# plc_module_xs_00001_001_Power.net
KiCad netlist of a schematic drawn in Altium Designer
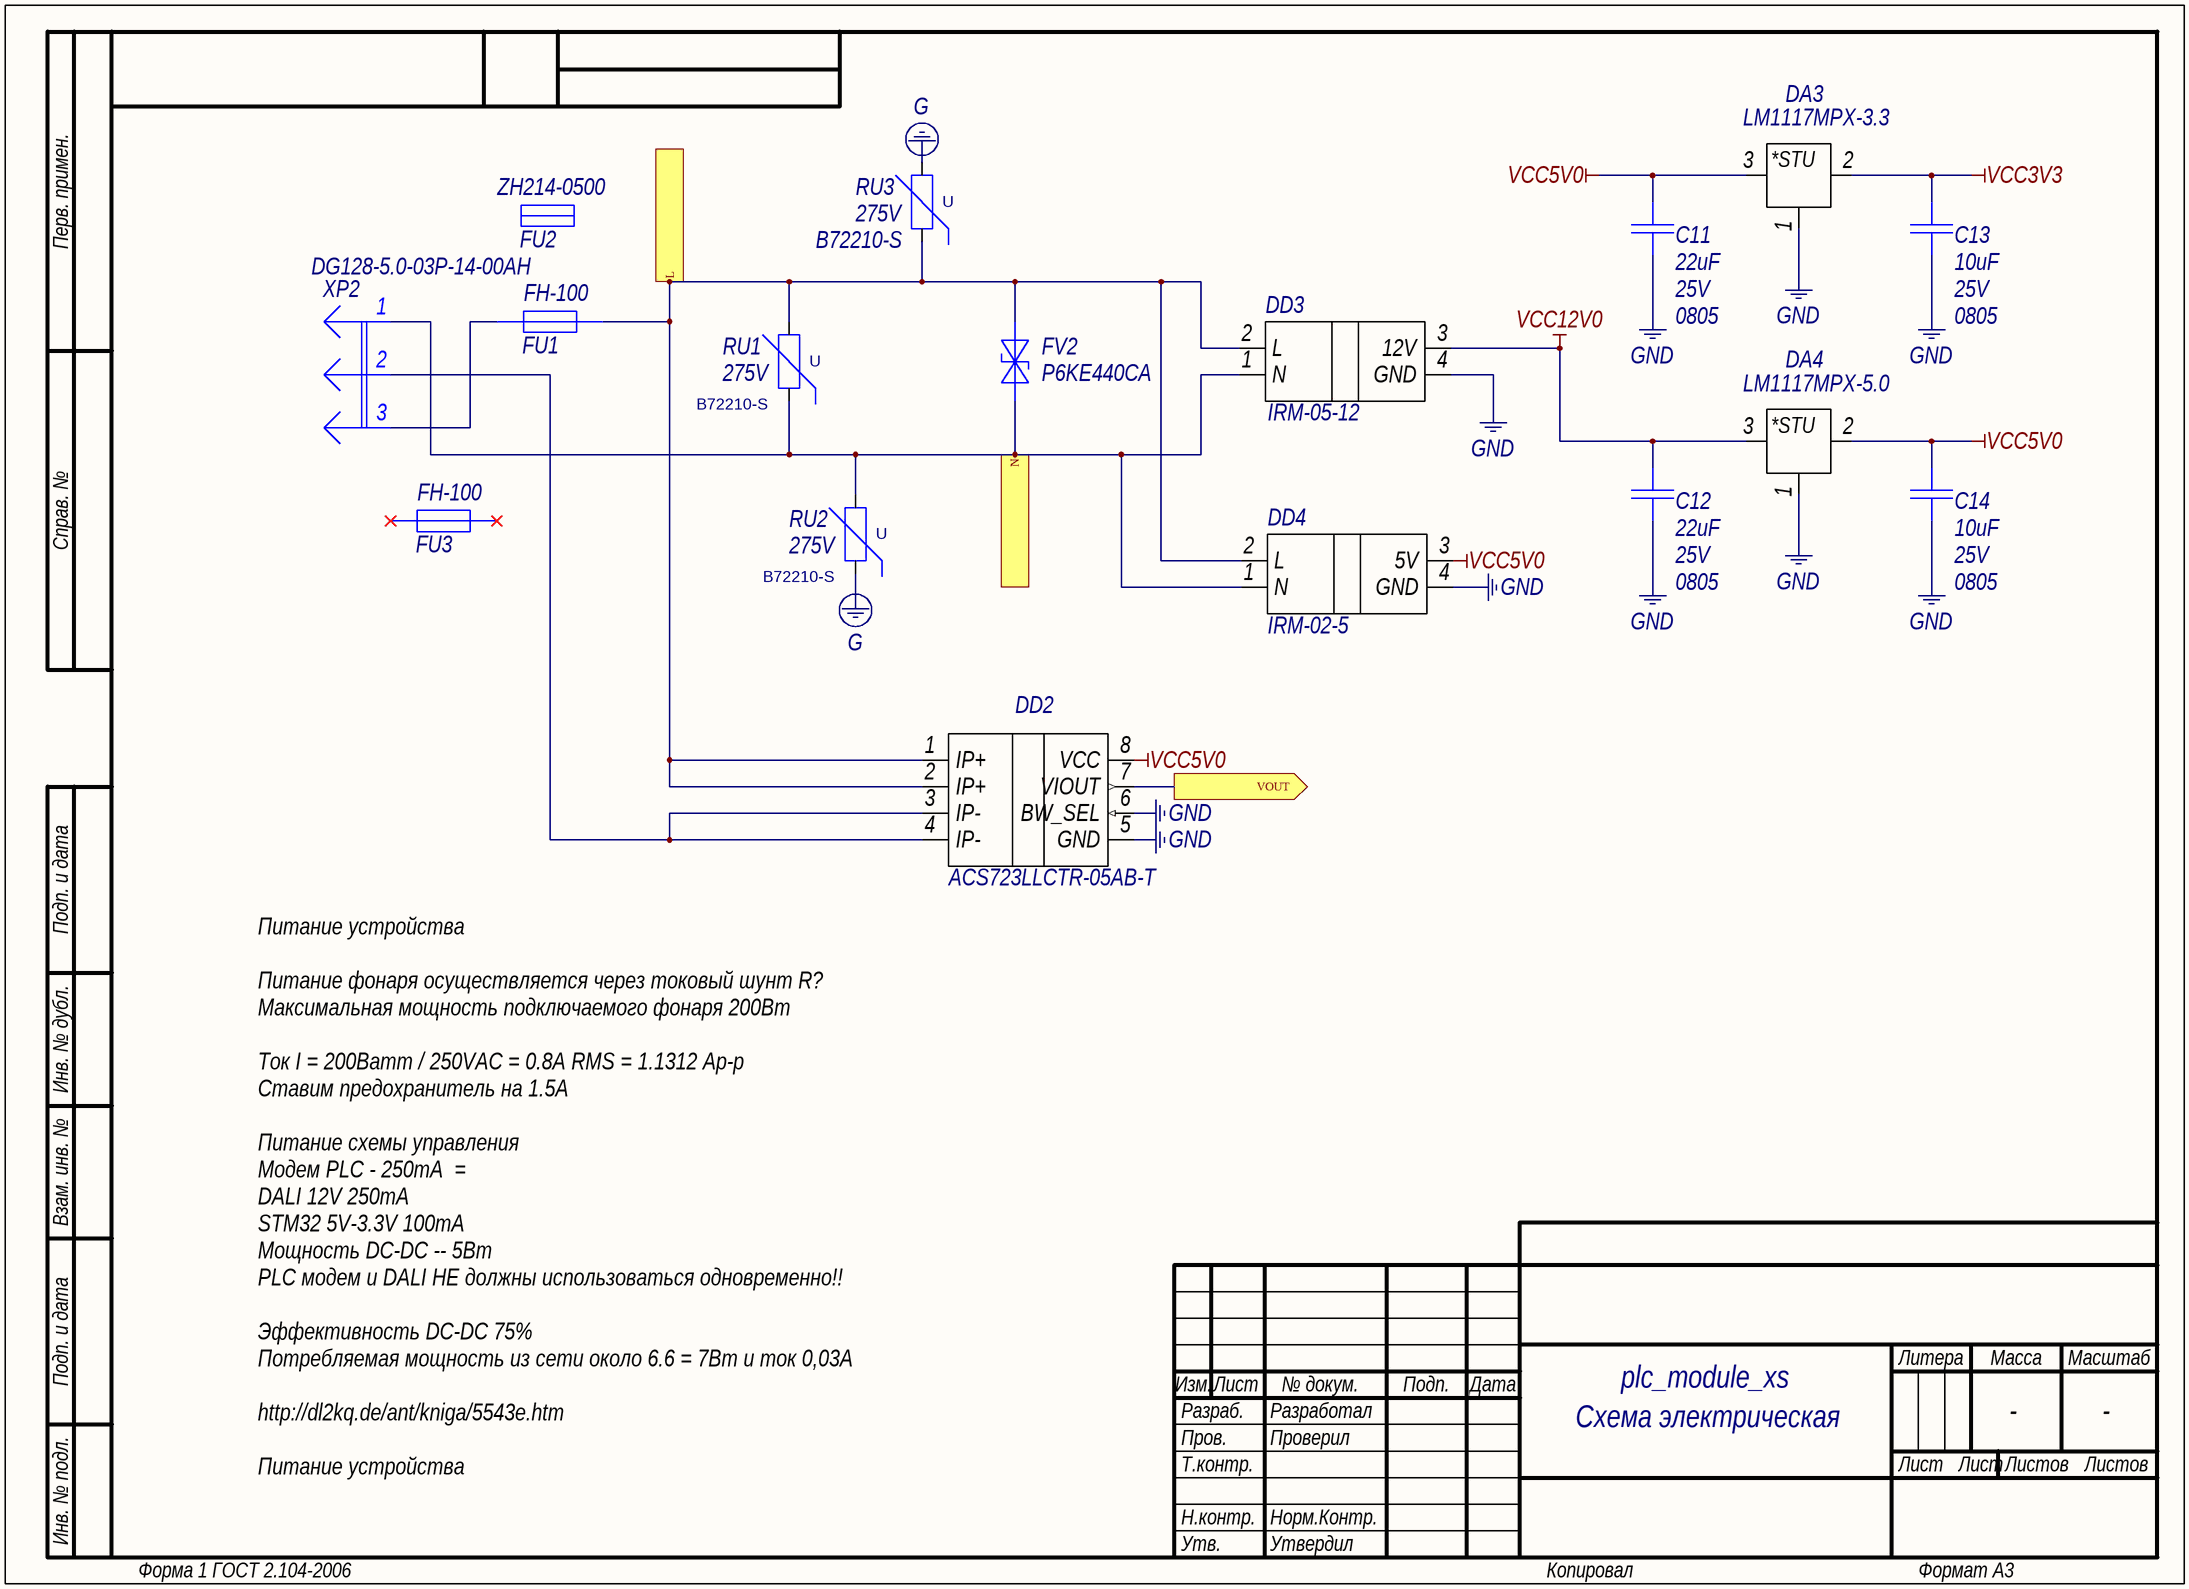
[diagram p0: plc_module_xs.00001.001_Power.SchDoc]

(export (version "E")
  (design (tool "Eeschema 10.0.6"))
  (components
    (comp (ref "C11")
      (value "22uF")
      (footprint "0805")
      (fields
        (field (name "PART NUMBER") "GRM21BR61E226ME44L")
        (field (name "VOLTAGE") "25V")
        (field (name "TOLERANCE") "±20%")
        (field (name "MANUFACTURER") "Murata")
        (field (name "PUBLISHER") "Andrew Danich")
      )
      (libsource (lib "GOST_IMPORT_PARTS") (part "Capacitor"))
    )
    (comp (ref "C12")
      (value "22uF")
      (footprint "0805")
      (fields
        (field (name "PART NUMBER") "GRM21BR61E226ME44L")
        (field (name "VOLTAGE") "25V")
        (field (name "TOLERANCE") "±20%")
        (field (name "MANUFACTURER") "Murata")
        (field (name "PUBLISHER") "Andrew Danich")
      )
      (libsource (lib "GOST_IMPORT_PARTS") (part "Capacitor"))
    )
    (comp (ref "C13")
      (value "10uF")
      (footprint "0805")
      (fields
        (field (name "PART NUMBER") "GRM21BR61E106KA73L")
        (field (name "VOLTAGE") "25V")
        (field (name "TOLERANCE") "±10%")
        (field (name "MANUFACTURER") "Murata")
        (field (name "PUBLISHER") "Andrew Danich")
      )
      (libsource (lib "GOST_IMPORT_PARTS") (part "Capacitor"))
    )
    (comp (ref "C14")
      (value "10uF")
      (footprint "0805")
      (fields
        (field (name "PART NUMBER") "GRM21BR61E106KA73L")
        (field (name "VOLTAGE") "25V")
        (field (name "TOLERANCE") "±10%")
        (field (name "MANUFACTURER") "Murata")
        (field (name "PUBLISHER") "Andrew Danich")
      )
      (libsource (lib "GOST_IMPORT_PARTS") (part "Capacitor"))
    )
    (comp (ref "DA3")
      (value "LM1117MPX-3.3")
      (footprint "SOT-223")
      (fields (field (name "Comment") "LM1117-Series") (field (name "PUBLISHER") "Andrew Danich"))
      (libsource (lib "GOST_IMPORT_PARTS") (part "LM1117-Series"))
    )
    (comp (ref "DA4")
      (value "LM1117MPX-5.0")
      (footprint "SOT-223")
      (fields (field (name "Comment") "LM1117-Series") (field (name "PUBLISHER") "Andrew Danich"))
      (libsource (lib "GOST_IMPORT_PARTS") (part "LM1117-Series"))
    )
    (comp (ref "DD2")
      (value "ACS723LLCTR-05AB-T")
      (footprint "SOIC-8")
      (fields (field (name "PART NUMBER") "ACS723LLCTR-05AB-T") (field (name "PUBLISHER") "Andrew Danich"))
      (libsource (lib "GOST_IMPORT_PARTS") (part "ACS723LLC"))
    )
    (comp (ref "DD3")
      (value "IRM-05-12")
      (footprint "IRM-05-12")
      (fields (field (name "POWER") "5W") (field (name "MANUFACTURER") "Mean Well (MW)"))
      (libsource (lib "GOST_IMPORT_PARTS") (part "IRM-05-12"))
    )
    (comp (ref "DD4")
      (value "IRM-02-5")
      (footprint "IRM-02-5")
      (fields (field (name "POWER") "2W") (field (name "MANUFACTURER") "Mean Well (MW)"))
      (libsource (lib "GOST_IMPORT_PARTS") (part "IRM-02-5"))
    )
    (comp (ref "FU1")
      (value "FH-100")
      (footprint "F-W20.0/E5.0")
      (fields (field (name "Comment") "Fuse") (field (name "PUBLISHER") "Andrew Danich"))
      (libsource (lib "GOST_IMPORT_PARTS") (part "Fuse"))
    )
    (comp (ref "FU2")
      (value "ZH214-0500")
      (footprint "FUSE_SCHURTER_FSF5X20")
      (fields (field (name "MANUFACTURER") "Zhenhui") (field (name "PUBLISHER") "Andrew Danich"))
      (libsource (lib "GOST_IMPORT_PARTS") (part "Fuse_1"))
    )
    (comp (ref "FU3")
      (value "FH-100")
      (footprint "F-W20.0/E5.0")
      (fields (field (name "Comment") "Fuse") (field (name "PUBLISHER") "Andrew Danich"))
      (libsource (lib "GOST_IMPORT_PARTS") (part "Fuse"))
    )
    (comp (ref "FV2")
      (value "P6KE440CA")
      (footprint "DO-15")
      (fields (field (name "PART NUMBER") "P6KE440CA") (field (name "PUBLISHER") "Andrew Danich"))
      (libsource (lib "GOST_IMPORT_PARTS") (part "Suppressor-Bi"))
    )
    (comp (ref "RU1")
      (value "B72210-S")
      (footprint "VAR_EPCOS_B72210S0461K101")
      (description "B72210-S 271-K101")
      (fields (field (name "MAX CONTINUOUS VOLTAGE (RMS)") "275V"))
      (libsource (lib "GOST_IMPORT_PARTS") (part "RU-I"))
    )
    (comp (ref "RU2")
      (value "B72210-S")
      (footprint "VAR_EPCOS_B72210S0461K101")
      (description "B72210-S 271-K101")
      (fields (field (name "MAX CONTINUOUS VOLTAGE (RMS)") "275V"))
      (libsource (lib "GOST_IMPORT_PARTS") (part "RU-I"))
    )
    (comp (ref "RU3")
      (value "B72210-S")
      (footprint "VAR_EPCOS_B72210S0461K101")
      (description "B72210-S 271-K101")
      (fields (field (name "MAX CONTINUOUS VOLTAGE (RMS)") "275V"))
      (libsource (lib "GOST_IMPORT_PARTS") (part "RU-I"))
    )
    (comp (ref "XP2")
      (value "DG128-5.0-03P-14-00AH")
      (footprint "PHOENIX_1715734")
      (fields (field (name "Comment") "LIN LOUT N") (field (name "PUBLISHER") "Andrew Danich"))
      (libsource (lib "GOST_IMPORT_PARTS") (part "Con-3-M"))
    )
  )
  (nets
    (net (code "1") (name "/L") (class "Default")
      (node (ref "DD2") (pin "1") (pinfunction "IP+_1") (pintype "power_in"))
      (node (ref "DD2") (pin "2") (pinfunction "IP+_2") (pintype "power_in"))
      (node (ref "DD3") (pin "2") (pinfunction "L_2") (pintype "passive"))
      (node (ref "DD4") (pin "2") (pinfunction "L_2") (pintype "passive"))
      (node (ref "FU1") (pin "2") (pinfunction "2_2") (pintype "passive"))
      (node (ref "FV2") (pin "2") (pinfunction "К_2") (pintype "passive"))
      (node (ref "RU1") (pin "1") (pintype "passive"))
      (node (ref "RU3") (pin "2") (pintype "passive"))
    )
    (net (code "2") (name "/N") (class "Default")
      (node (ref "DD3") (pin "1") (pinfunction "N_1") (pintype "passive"))
      (node (ref "DD4") (pin "1") (pinfunction "N_1") (pintype "passive"))
      (node (ref "FV2") (pin "1") (pinfunction "А_1") (pintype "passive"))
      (node (ref "RU1") (pin "2") (pintype "passive"))
      (node (ref "RU2") (pin "1") (pintype "passive"))
      (node (ref "XP2") (pin "1") (pintype "passive"))
    )
    (net (code "3") (name "/VOUT") (class "Default")
      (node (ref "DD2") (pin "7") (pinfunction "VIOUT_7") (pintype "output"))
    )
    (net (code "4") (name "G") (class "Default")
      (node (ref "RU2") (pin "2") (pintype "passive"))
      (node (ref "RU3") (pin "1") (pintype "passive"))
    )
    (net (code "5") (name "GND") (class "Default")
      (node (ref "C11") (pin "1") (pinfunction "1_1") (pintype "passive"))
      (node (ref "C12") (pin "1") (pinfunction "1_1") (pintype "passive"))
      (node (ref "C13") (pin "1") (pinfunction "1_1") (pintype "passive"))
      (node (ref "C14") (pin "1") (pinfunction "1_1") (pintype "passive"))
      (node (ref "DA3") (pin "1") (pinfunction "Adj/GND_1") (pintype "passive"))
      (node (ref "DA4") (pin "1") (pinfunction "Adj/GND_1") (pintype "passive"))
      (node (ref "DD2") (pin "5") (pinfunction "GND_5") (pintype "power_in"))
      (node (ref "DD2") (pin "6") (pinfunction "BW_SEL_6") (pintype "input"))
      (node (ref "DD3") (pin "4") (pinfunction "GND_4") (pintype "passive"))
      (node (ref "DD4") (pin "4") (pinfunction "GND_4") (pintype "passive"))
    )
    (net (code "6") (name "Net-(DD2-IP--Pad3)") (class "Default")
      (node (ref "DD2") (pin "3") (pinfunction "IP-_3") (pintype "power_in"))
      (node (ref "DD2") (pin "4") (pinfunction "IP-_4") (pintype "power_in"))
      (node (ref "XP2") (pin "2") (pintype "passive"))
    )
    (net (code "7") (name "Net-(FU1-Pad1)") (class "Default")
      (node (ref "FU1") (pin "1") (pinfunction "1_1") (pintype "passive"))
      (node (ref "XP2") (pin "3") (pintype "passive"))
    )
    (net (code "8") (name "VCC3V3") (class "Default")
      (node (ref "C13") (pin "2") (pinfunction "2_2") (pintype "passive"))
      (node (ref "DA3") (pin "2") (pinfunction "Out_2") (pintype "passive"))
    )
    (net (code "9") (name "VCC5V0") (class "Default")
      (node (ref "C11") (pin "2") (pinfunction "2_2") (pintype "passive"))
      (node (ref "C14") (pin "2") (pinfunction "2_2") (pintype "passive"))
      (node (ref "DA3") (pin "3") (pinfunction "In_3") (pintype "passive"))
      (node (ref "DA4") (pin "2") (pinfunction "Out_2") (pintype "passive"))
      (node (ref "DD2") (pin "8") (pinfunction "VCC_8") (pintype "power_in"))
      (node (ref "DD4") (pin "3") (pinfunction "5V_3") (pintype "passive"))
    )
    (net (code "10") (name "VCC12V0") (class "Default")
      (node (ref "C12") (pin "2") (pinfunction "2_2") (pintype "passive"))
      (node (ref "DA4") (pin "3") (pinfunction "In_3") (pintype "passive"))
      (node (ref "DD3") (pin "3") (pinfunction "12V_3") (pintype "passive"))
    )
    (net (code "11") (name "unconnected-(FU3-Pad1)") (class "Default")
      (node (ref "FU3") (pin "1") (pinfunction "1_1") (pintype "passive+no_connect"))
    )
    (net (code "12") (name "unconnected-(FU3-Pad2)") (class "Default")
      (node (ref "FU3") (pin "2") (pinfunction "2_2") (pintype "passive+no_connect"))
    )
  )
)
